# AutomaticSanitizer.net
KiCad netlist of a schematic drawn in EAGLE
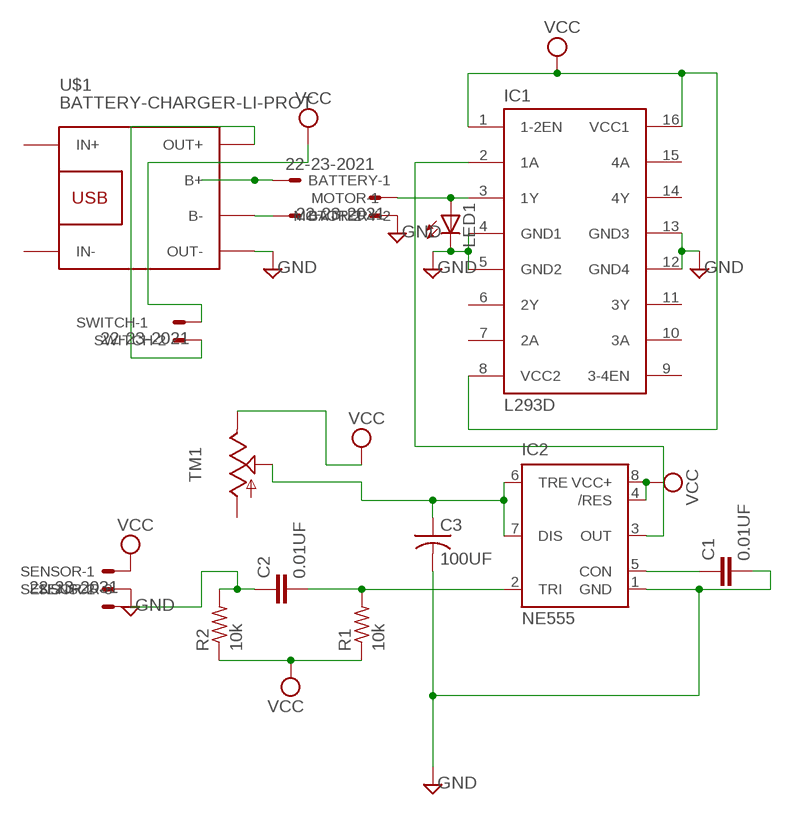
[diagram p0: schematic, sheet 1]

(export (version "E")
  (design (tool "Eeschema 10.0.6"))
  (components
    (comp (ref "BATTERY")
      (value "22-23-2021")
      (footprint "eagle-import:22-23-2021")
      (fields (field (name "MF") "MOLEX"))
      (libsource (lib "eagle-import") (part "22-23-2021"))
    )
    (comp (ref "C1")
      (value "0.01UF")
      (footprint "eagle-import:C2.5-2")
      (libsource (lib "eagle-import") (part "C2.5/2"))
    )
    (comp (ref "C2")
      (value "0.01UF")
      (footprint "eagle-import:C2.5-2")
      (libsource (lib "eagle-import") (part "C2.5/2"))
    )
    (comp (ref "C3")
      (value "100UF")
      (footprint "eagle-import:C025-025X050")
      (libsource (lib "eagle-import") (part "C-US025-025X050"))
    )
    (comp (ref "IC1")
      (value "L293D")
      (footprint "eagle-import:DIL16")
      (libsource (lib "eagle-import") (part "L293D"))
    )
    (comp (ref "IC2")
      (value "NE555")
      (footprint "eagle-import:DIL-08")
      (fields (field (name "MF") "Arrow Electronics") (field (name "MPN") "NE555N"))
      (libsource (lib "eagle-import") (part "NE555"))
    )
    (comp (ref "LED1")
      (value "LED5MM")
      (footprint "eagle-import:LED5MM")
      (libsource (lib "eagle-import") (part "LED5MM"))
    )
    (comp (ref "MOTOR")
      (value "22-23-2021")
      (footprint "eagle-import:22-23-2021")
      (fields (field (name "MF") "MOLEX"))
      (libsource (lib "eagle-import") (part "22-23-2021"))
    )
    (comp (ref "R1")
      (value "10k")
      (footprint "eagle-import:0204_5")
      (libsource (lib "eagle-import") (part "R-US_0204/5"))
    )
    (comp (ref "R2")
      (value "10k")
      (footprint "eagle-import:0204_5")
      (libsource (lib "eagle-import") (part "R-US_0204/5"))
    )
    (comp (ref "SENSOR")
      (value "22-23-2031")
      (footprint "eagle-import:22-23-2031")
      (fields (field (name "MF") "MOLEX"))
      (libsource (lib "eagle-import") (part "22-23-2031"))
    )
    (comp (ref "SWITCH")
      (value "22-23-2021")
      (footprint "eagle-import:22-23-2021")
      (fields (field (name "MF") "MOLEX"))
      (libsource (lib "eagle-import") (part "22-23-2021"))
    )
    (comp (ref "TM1")
      (value "TRIM")
      (footprint "eagle-import:6MM")
      (libsource (lib "eagle-import") (part "TRIM"))
    )
    (comp (ref "U$1")
      (value "BATTERY-CHARGER-LI-PROT")
      (footprint "eagle-import:BATTERY-CHARGER-LI-PROT")
      (libsource (lib "eagle-import") (part "BATTERY-CHARGER-LI-PROT"))
    )
  )
  (nets
    (net (code "1") (name "GND") (class "Default")
      (node (ref "C1") (pin "2") (pinfunction "2_2") (pintype "passive"))
      (node (ref "C3") (pin "2") (pinfunction "2_2") (pintype "passive"))
      (node (ref "IC1") (pin "12") (pinfunction "GND4_12") (pintype "power_in"))
      (node (ref "IC1") (pin "13") (pinfunction "GND3_13") (pintype "power_in"))
      (node (ref "IC1") (pin "4") (pinfunction "GND1_4") (pintype "power_in"))
      (node (ref "IC1") (pin "5") (pinfunction "GND2_5") (pintype "power_in"))
      (node (ref "IC2") (pin "1") (pinfunction "GND_1") (pintype "power_in"))
      (node (ref "LED1") (pin "K") (pinfunction "C_K") (pintype "passive"))
      (node (ref "MOTOR") (pin "2") (pinfunction "S_2") (pintype "passive"))
      (node (ref "SENSOR") (pin "2") (pinfunction "S_2") (pintype "passive"))
      (node (ref "U$1") (pin "OUT-") (pinfunction "OUT-_OUT-") (pintype "bidirectional"))
    )
    (net (code "2") (name "Net-(BATTERYA-S)") (class "Default")
      (node (ref "BATTERY") (pin "1") (pinfunction "S_1") (pintype "passive"))
      (node (ref "U$1") (pin "B+") (pinfunction "B+_B+") (pintype "bidirectional"))
    )
    (net (code "3") (name "Net-(BATTERYB-S)") (class "Default")
      (node (ref "BATTERY") (pin "2") (pinfunction "S_2") (pintype "passive"))
      (node (ref "U$1") (pin "B-") (pinfunction "B-_B-") (pintype "bidirectional"))
    )
    (net (code "4") (name "Net-(IC1-1A)") (class "Default")
      (node (ref "IC1") (pin "2") (pinfunction "1A_2") (pintype "input"))
      (node (ref "IC2") (pin "3") (pinfunction "OUT_3") (pintype "output"))
    )
    (net (code "5") (name "Net-(IC1-1Y)") (class "Default")
      (node (ref "IC1") (pin "3") (pinfunction "1Y_3") (pintype "output"))
      (node (ref "LED1") (pin "A") (pinfunction "A_A") (pintype "passive"))
      (node (ref "MOTOR") (pin "1") (pinfunction "S_1") (pintype "passive"))
    )
    (net (code "6") (name "Net-(IC2-CON)") (class "Default")
      (node (ref "C1") (pin "1") (pinfunction "1_1") (pintype "passive"))
      (node (ref "IC2") (pin "5") (pinfunction "CON_5") (pintype "input"))
    )
    (net (code "7") (name "Net-(IC2-DIS)") (class "Default")
      (node (ref "C3") (pin "1") (pinfunction "1_1") (pintype "passive"))
      (node (ref "IC2") (pin "6") (pinfunction "TRE_6") (pintype "input"))
      (node (ref "IC2") (pin "7") (pinfunction "DIS_7") (pintype "input"))
      (node (ref "TM1") (pin "S") (pinfunction "S_S") (pintype "passive"))
    )
    (net (code "8") (name "Net-(IC2-TRI)") (class "Default")
      (node (ref "C2") (pin "2") (pinfunction "2_2") (pintype "passive"))
      (node (ref "IC2") (pin "2") (pinfunction "TRI_2") (pintype "input"))
      (node (ref "R1") (pin "2") (pinfunction "2_2") (pintype "passive"))
    )
    (net (code "9") (name "Net-(SENSORC-S)") (class "Default")
      (node (ref "C2") (pin "1") (pinfunction "1_1") (pintype "passive"))
      (node (ref "R2") (pin "2") (pinfunction "2_2") (pintype "passive"))
      (node (ref "SENSOR") (pin "3") (pinfunction "S_3") (pintype "passive"))
    )
    (net (code "10") (name "Net-(SWITCHB-S)") (class "Default")
      (node (ref "SWITCH") (pin "2") (pinfunction "S_2") (pintype "passive"))
      (node (ref "U$1") (pin "OUT+") (pinfunction "OUT+_OUT+") (pintype "bidirectional"))
    )
    (net (code "11") (name "VCC") (class "Default")
      (node (ref "IC1") (pin "1") (pinfunction "1-2EN_1") (pintype "input"))
      (node (ref "IC1") (pin "16") (pinfunction "VCC1_16") (pintype "power_in"))
      (node (ref "IC1") (pin "8") (pinfunction "VCC2_8") (pintype "power_in"))
      (node (ref "IC2") (pin "4") (pinfunction "/RES_4") (pintype "input"))
      (node (ref "IC2") (pin "8") (pinfunction "VCC+_8") (pintype "power_in"))
      (node (ref "R1") (pin "1") (pinfunction "1_1") (pintype "passive"))
      (node (ref "R2") (pin "1") (pinfunction "1_1") (pintype "passive"))
      (node (ref "SENSOR") (pin "1") (pinfunction "S_1") (pintype "passive"))
      (node (ref "SWITCH") (pin "1") (pinfunction "S_1") (pintype "passive"))
      (node (ref "TM1") (pin "E") (pinfunction "E_E") (pintype "passive"))
    )
    (net (code "12") (name "unconnected-(IC1-2A-Pad7)") (class "Default")
      (node (ref "IC1") (pin "7") (pinfunction "2A_7") (pintype "input"))
    )
    (net (code "13") (name "unconnected-(IC1-2Y-Pad6)") (class "Default")
      (node (ref "IC1") (pin "6") (pinfunction "2Y_6") (pintype "output"))
    )
    (net (code "14") (name "unconnected-(IC1-3-4EN-Pad9)") (class "Default")
      (node (ref "IC1") (pin "9") (pinfunction "3-4EN_9") (pintype "input"))
    )
    (net (code "15") (name "unconnected-(IC1-3A-Pad10)") (class "Default")
      (node (ref "IC1") (pin "10") (pinfunction "3A_10") (pintype "input"))
    )
    (net (code "16") (name "unconnected-(IC1-3Y-Pad11)") (class "Default")
      (node (ref "IC1") (pin "11") (pinfunction "3Y_11") (pintype "output"))
    )
    (net (code "17") (name "unconnected-(IC1-4A-Pad15)") (class "Default")
      (node (ref "IC1") (pin "15") (pinfunction "4A_15") (pintype "input"))
    )
    (net (code "18") (name "unconnected-(IC1-4Y-Pad14)") (class "Default")
      (node (ref "IC1") (pin "14") (pinfunction "4Y_14") (pintype "output"))
    )
    (net (code "19") (name "unconnected-(TM1-PadA)") (class "Default")
      (node (ref "TM1") (pin "A") (pinfunction "A_A") (pintype "passive"))
    )
    (net (code "20") (name "unconnected-(U$1-PadIN+)") (class "Default")
      (node (ref "U$1") (pin "IN+") (pinfunction "IN+_IN+") (pintype "bidirectional"))
    )
    (net (code "21") (name "unconnected-(U$1-PadIN-)") (class "Default")
      (node (ref "U$1") (pin "IN-") (pinfunction "IN-_IN-") (pintype "bidirectional"))
    )
  )
)
